# LED-Rectifier-v003.net
KiCad netlist of a schematic drawn in EAGLE
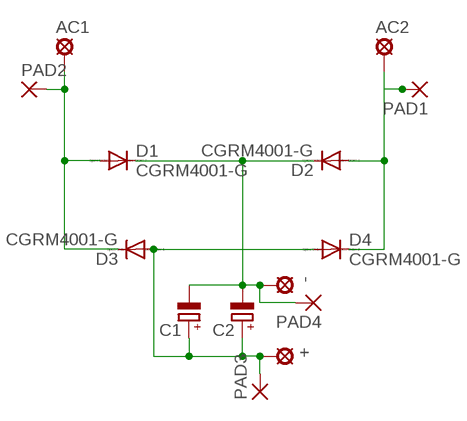
[diagram p0: schematic, sheet 1]

(export (version "E")
  (design (tool "Eeschema 10.0.6"))
  (components
    (comp (ref "+")
      (value "SE14")
      (footprint "eagle-import:SE14")
      (libsource (lib "eagle-import") (part "SE14"))
    )
    (comp (ref "-")
      (value "SE14")
      (footprint "eagle-import:SE14")
      (libsource (lib "eagle-import") (part "SE14"))
    )
    (comp (ref "AC1")
      (value "SE14")
      (footprint "eagle-import:SE14")
      (libsource (lib "eagle-import") (part "SE14"))
    )
    (comp (ref "AC2")
      (value "SE14")
      (footprint "eagle-import:SE14")
      (libsource (lib "eagle-import") (part "SE14"))
    )
    (comp (ref "C1")
      (value "CPOL-EU085CS-1AW")
      (footprint "eagle-import:085CS_1AW")
      (libsource (lib "eagle-import") (part "CPOL-EU085CS-1AW"))
    )
    (comp (ref "C2")
      (value "CPOL-EUE3.5-10")
      (footprint "eagle-import:E3,5-10")
      (libsource (lib "eagle-import") (part "CPOL-EUE3.5-10"))
    )
    (comp (ref "D1")
      (value "CGRM4001-G")
      (footprint "eagle-import:SOD-123_MINI-SMA")
      (libsource (lib "eagle-import") (part "CGRM400-G1"))
    )
    (comp (ref "D2")
      (value "CGRM4001-G")
      (footprint "eagle-import:SOD-123_MINI-SMA")
      (libsource (lib "eagle-import") (part "CGRM400-G1"))
    )
    (comp (ref "D3")
      (value "CGRM4001-G")
      (footprint "eagle-import:SOD-123_MINI-SMA")
      (libsource (lib "eagle-import") (part "CGRM400-G1"))
    )
    (comp (ref "D4")
      (value "CGRM4001-G")
      (footprint "eagle-import:SOD-123_MINI-SMA")
      (libsource (lib "eagle-import") (part "CGRM400-G1"))
    )
    (comp (ref "PAD1")
      (value "SMD5")
      (footprint "eagle-import:SMD2,54-5,08")
      (libsource (lib "eagle-import") (part "SMD5"))
    )
    (comp (ref "PAD2")
      (value "SMD5")
      (footprint "eagle-import:SMD2,54-5,08")
      (libsource (lib "eagle-import") (part "SMD5"))
    )
    (comp (ref "PAD3")
      (value "SMD5")
      (footprint "eagle-import:SMD2,54-5,08")
      (libsource (lib "eagle-import") (part "SMD5"))
    )
    (comp (ref "PAD4")
      (value "SMD5")
      (footprint "eagle-import:SMD2,54-5,08")
      (libsource (lib "eagle-import") (part "SMD5"))
    )
  )
  (nets
    (net (code "1") (name "Net-(PAD1-P)") (class "Default")
      (node (ref "AC2") (pin "MP") (pinfunction "MP_MP") (pintype "passive"))
      (node (ref "D2") (pin "A") (pinfunction "A_A") (pintype "passive"))
      (node (ref "D4") (pin "C") (pinfunction "C_C") (pintype "passive"))
      (node (ref "PAD1") (pin "1") (pinfunction "P_1") (pintype "passive"))
    )
    (net (code "2") (name "Net-(PAD2-P)") (class "Default")
      (node (ref "AC1") (pin "MP") (pinfunction "MP_MP") (pintype "passive"))
      (node (ref "D1") (pin "A") (pinfunction "A_A") (pintype "passive"))
      (node (ref "D3") (pin "C") (pinfunction "C_C") (pintype "passive"))
      (node (ref "PAD2") (pin "1") (pinfunction "P_1") (pintype "passive"))
    )
    (net (code "3") (name "Net-(PAD3-P)") (class "Default")
      (node (ref "+") (pin "MP") (pinfunction "MP_MP") (pintype "passive"))
      (node (ref "C1") (pin "+") (pinfunction "+_+") (pintype "passive"))
      (node (ref "C2") (pin "+") (pinfunction "+_+") (pintype "passive"))
      (node (ref "D3") (pin "A") (pinfunction "A_A") (pintype "passive"))
      (node (ref "D4") (pin "A") (pinfunction "A_A") (pintype "passive"))
      (node (ref "PAD3") (pin "1") (pinfunction "P_1") (pintype "passive"))
    )
    (net (code "4") (name "Net-(PAD4-P)") (class "Default")
      (node (ref "-") (pin "MP") (pinfunction "MP_MP") (pintype "passive"))
      (node (ref "C1") (pin "-") (pinfunction "-_-") (pintype "passive"))
      (node (ref "C2") (pin "-") (pinfunction "-_-") (pintype "passive"))
      (node (ref "D1") (pin "C") (pinfunction "C_C") (pintype "passive"))
      (node (ref "D2") (pin "C") (pinfunction "C_C") (pintype "passive"))
      (node (ref "PAD4") (pin "1") (pinfunction "P_1") (pintype "passive"))
    )
  )
)
